# Potentiometer_ADC.net
KiCad netlist of a schematic drawn in EAGLE
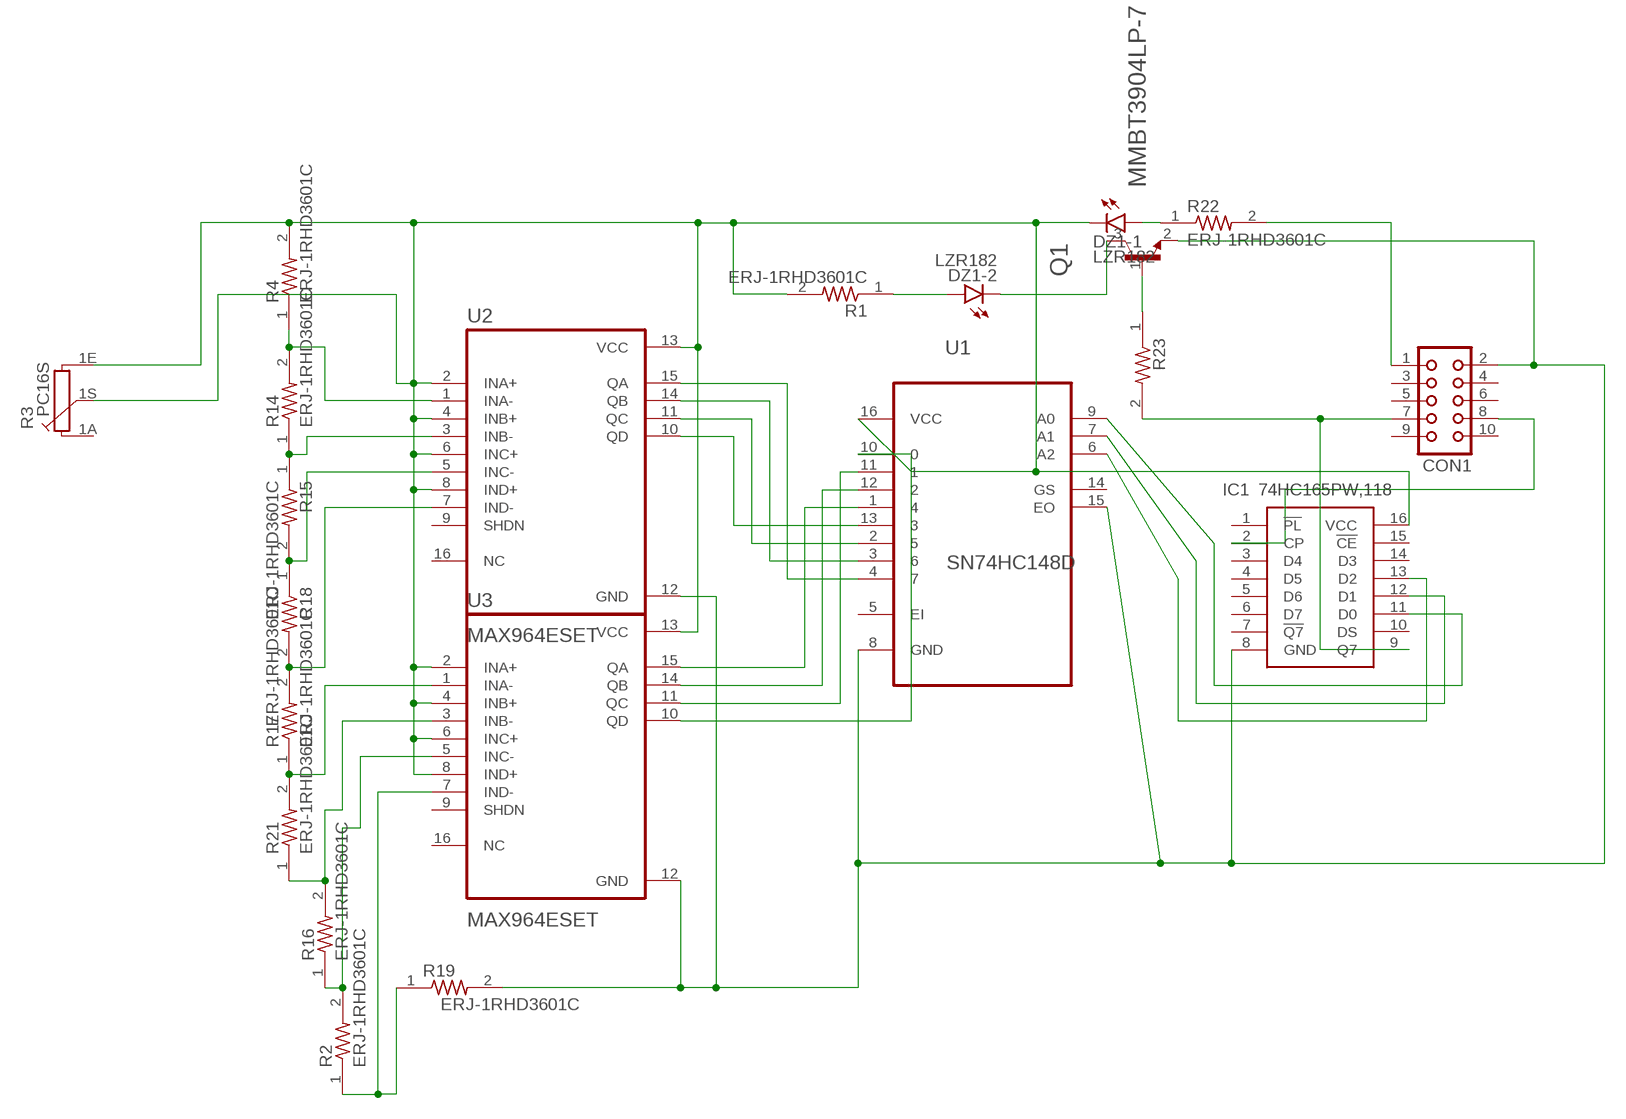
[diagram p0: schematic, sheet 1]

(export (version "E")
  (design (tool "Eeschema 10.0.6"))
  (components
    (comp (ref "CON1")
      (value "CON10L")
      (footprint "eagle-import:CON10L")
      (libsource (lib "eagle-import") (part "CON10L"))
    )
    (comp (ref "DZ1")
      (value "LZR182")
      (footprint "eagle-import:LZR182")
      (libsource (lib "eagle-import") (part "LZR182"))
    )
    (comp (ref "IC1")
      (value "74HC165PW,118")
      (footprint "eagle-import:SOP65P640X110-16N")
      (fields (field (name "MOUSER_PART_NUMBER") "771-74HC165PW-T"))
      (libsource (lib "eagle-import") (part "74HC165PW,118"))
    )
    (comp (ref "Q1")
      (value "MMBT3904LP-7")
      (footprint "eagle-import:DFN101X61X53-3N")
      (fields (field (name "DIGI-KEY_PART_NUMBER") "MMBT3904LP-7DICT-ND") (field (name "MF") "Diodes Inc."))
      (libsource (lib "eagle-import") (part "MMBT3904LP-7"))
    )
    (comp (ref "R1")
      (value "ERJ-1RHD3601C")
      (footprint "eagle-import:RESC0603X26N")
      (fields (field (name "MF") "Panasonic"))
      (libsource (lib "eagle-import") (part "ERJ-1RHD3601C"))
    )
    (comp (ref "R2")
      (value "ERJ-1RHD3601C")
      (footprint "eagle-import:RESC0603X26N")
      (fields (field (name "MF") "Panasonic"))
      (libsource (lib "eagle-import") (part "ERJ-1RHD3601C"))
    )
    (comp (ref "R3")
      (value "PC16S")
      (footprint "eagle-import:PC16S")
      (libsource (lib "eagle-import") (part "PC16S"))
    )
    (comp (ref "R4")
      (value "ERJ-1RHD3601C")
      (footprint "eagle-import:RESC0603X26N")
      (fields (field (name "MF") "Panasonic"))
      (libsource (lib "eagle-import") (part "ERJ-1RHD3601C"))
    )
    (comp (ref "R14")
      (value "ERJ-1RHD3601C")
      (footprint "eagle-import:RESC0603X26N")
      (fields (field (name "MF") "Panasonic"))
      (libsource (lib "eagle-import") (part "ERJ-1RHD3601C"))
    )
    (comp (ref "R15")
      (value "ERJ-1RHD3601C")
      (footprint "eagle-import:RESC0603X26N")
      (fields (field (name "MF") "Panasonic"))
      (libsource (lib "eagle-import") (part "ERJ-1RHD3601C"))
    )
    (comp (ref "R16")
      (value "ERJ-1RHD3601C")
      (footprint "eagle-import:RESC0603X26N")
      (fields (field (name "MF") "Panasonic"))
      (libsource (lib "eagle-import") (part "ERJ-1RHD3601C"))
    )
    (comp (ref "R17")
      (value "ERJ-1RHD3601C")
      (footprint "eagle-import:RESC0603X26N")
      (fields (field (name "MF") "Panasonic"))
      (libsource (lib "eagle-import") (part "ERJ-1RHD3601C"))
    )
    (comp (ref "R18")
      (value "ERJ-1RHD3601C")
      (footprint "eagle-import:RESC0603X26N")
      (fields (field (name "MF") "Panasonic"))
      (libsource (lib "eagle-import") (part "ERJ-1RHD3601C"))
    )
    (comp (ref "R19")
      (value "ERJ-1RHD3601C")
      (footprint "eagle-import:RESC0603X26N")
      (fields (field (name "MF") "Panasonic"))
      (libsource (lib "eagle-import") (part "ERJ-1RHD3601C"))
    )
    (comp (ref "R21")
      (value "ERJ-1RHD3601C")
      (footprint "eagle-import:RESC0603X26N")
      (fields (field (name "MF") "Panasonic"))
      (libsource (lib "eagle-import") (part "ERJ-1RHD3601C"))
    )
    (comp (ref "R22")
      (value "ERJ-1RHD3601C")
      (footprint "eagle-import:RESC0603X26N")
      (fields (field (name "MF") "Panasonic"))
      (libsource (lib "eagle-import") (part "ERJ-1RHD3601C"))
    )
    (comp (ref "R23")
      (value "ERJ-1RHD3601C")
      (footprint "eagle-import:RESC0603X26N")
      (fields (field (name "MF") "Panasonic"))
      (libsource (lib "eagle-import") (part "ERJ-1RHD3601C"))
    )
    (comp (ref "U1")
      (value "SN74HC148D")
      (footprint "eagle-import:SOIC127P600X175-16N")
      (fields (field (name "MF") "Texas Instruments"))
      (libsource (lib "eagle-import") (part "SN74HC148D"))
    )
    (comp (ref "U2")
      (value "MAX964ESET")
      (footprint "eagle-import:SOIC127P600X175-16N")
      (fields (field (name "MF") "Maxim Integrated") (field (name "MP") "MAX964ESE+"))
      (libsource (lib "eagle-import") (part "MAX964ESET"))
    )
    (comp (ref "U3")
      (value "MAX964ESET")
      (footprint "eagle-import:SOIC127P600X175-16N")
      (fields (field (name "MF") "Maxim Integrated") (field (name "MP") "MAX964ESE+"))
      (libsource (lib "eagle-import") (part "MAX964ESET"))
    )
  )
  (nets
    (net (code "1") (name "Net-(CON1-Pad1)") (class "Default")
      (node (ref "CON1") (pin "1") (pinfunction "1_1") (pintype "passive"))
      (node (ref "R22") (pin "2") (pinfunction "2_2") (pintype "passive"))
    )
    (net (code "2") (name "Net-(DZ1A-A)") (class "Default")
      (node (ref "DZ1") (pin "A1") (pinfunction "A_A1") (pintype "passive"))
      (node (ref "R22") (pin "1") (pinfunction "1_1") (pintype "passive"))
    )
    (net (code "3") (name "Net-(DZ1A-C)") (class "Default")
      (node (ref "DZ1") (pin "K1") (pinfunction "C_K1") (pintype "passive"))
      (node (ref "IC1") (pin "16") (pinfunction "VCC_16") (pintype "bidirectional"))
      (node (ref "R1") (pin "2") (pinfunction "2_2") (pintype "passive"))
      (node (ref "R3") (pin "1E") (pinfunction "1E_1E") (pintype "passive"))
      (node (ref "R3") (pin "1S") (pinfunction "1S_1S") (pintype "passive"))
      (node (ref "R4") (pin "2") (pinfunction "2_2") (pintype "passive"))
      (node (ref "U1") (pin "16") (pinfunction "VCC_16") (pintype "power_in"))
      (node (ref "U2") (pin "13") (pinfunction "VCC_13") (pintype "power_in"))
      (node (ref "U2") (pin "2") (pinfunction "INA+_2") (pintype "input"))
      (node (ref "U2") (pin "4") (pinfunction "INB+_4") (pintype "input"))
      (node (ref "U2") (pin "6") (pinfunction "INC+_6") (pintype "input"))
      (node (ref "U2") (pin "8") (pinfunction "IND+_8") (pintype "input"))
      (node (ref "U3") (pin "13") (pinfunction "VCC_13") (pintype "power_in"))
      (node (ref "U3") (pin "2") (pinfunction "INA+_2") (pintype "input"))
      (node (ref "U3") (pin "4") (pinfunction "INB+_4") (pintype "input"))
      (node (ref "U3") (pin "6") (pinfunction "INC+_6") (pintype "input"))
      (node (ref "U3") (pin "8") (pinfunction "IND+_8") (pintype "input"))
    )
    (net (code "4") (name "Net-(DZ1B-A)") (class "Default")
      (node (ref "DZ1") (pin "A2") (pinfunction "A_A2") (pintype "passive"))
      (node (ref "R1") (pin "1") (pinfunction "1_1") (pintype "passive"))
    )
    (net (code "5") (name "Net-(DZ1B-C)") (class "Default")
      (node (ref "DZ1") (pin "K2") (pinfunction "C_K2") (pintype "passive"))
      (node (ref "Q1") (pin "3") (pinfunction "C_3") (pintype "passive"))
    )
    (net (code "6") (name "Net-(IC1-CP)") (class "Default")
      (node (ref "CON1") (pin "8") (pinfunction "8_8") (pintype "passive"))
      (node (ref "IC1") (pin "2") (pinfunction "CP_2") (pintype "bidirectional"))
    )
    (net (code "7") (name "Net-(IC1-D0)") (class "Default")
      (node (ref "IC1") (pin "11") (pinfunction "D0_11") (pintype "bidirectional"))
      (node (ref "U1") (pin "9") (pinfunction "A0_9") (pintype "output"))
    )
    (net (code "8") (name "Net-(IC1-D1)") (class "Default")
      (node (ref "IC1") (pin "12") (pinfunction "D1_12") (pintype "bidirectional"))
      (node (ref "U1") (pin "7") (pinfunction "A1_7") (pintype "output"))
    )
    (net (code "9") (name "Net-(IC1-D2)") (class "Default")
      (node (ref "IC1") (pin "13") (pinfunction "D2_13") (pintype "bidirectional"))
      (node (ref "U1") (pin "6") (pinfunction "A2_6") (pintype "output"))
    )
    (net (code "10") (name "Net-(IC1-GND)") (class "Default")
      (node (ref "CON1") (pin "2") (pinfunction "2_2") (pintype "passive"))
      (node (ref "IC1") (pin "8") (pinfunction "GND_8") (pintype "bidirectional"))
      (node (ref "Q1") (pin "2") (pinfunction "E_2") (pintype "passive"))
      (node (ref "R19") (pin "2") (pinfunction "2_2") (pintype "passive"))
      (node (ref "U1") (pin "15") (pinfunction "EO_15") (pintype "output"))
      (node (ref "U1") (pin "8") (pinfunction "GND_8") (pintype "passive"))
      (node (ref "U2") (pin "12") (pinfunction "GND_12") (pintype "power_in"))
      (node (ref "U3") (pin "12") (pinfunction "GND_12") (pintype "power_in"))
    )
    (net (code "11") (name "Net-(IC1-Q7)") (class "Default")
      (node (ref "CON1") (pin "7") (pinfunction "7_7") (pintype "passive"))
      (node (ref "IC1") (pin "9") (pinfunction "Q7_9") (pintype "bidirectional"))
      (node (ref "R23") (pin "2") (pinfunction "2_2") (pintype "passive"))
    )
    (net (code "12") (name "Net-(Q1-B)") (class "Default")
      (node (ref "Q1") (pin "1") (pinfunction "B_1") (pintype "passive"))
      (node (ref "R23") (pin "1") (pinfunction "1_1") (pintype "passive"))
    )
    (net (code "13") (name "Net-(U1-0)") (class "Default")
      (node (ref "U1") (pin "10") (pinfunction "0_10") (pintype "input"))
      (node (ref "U3") (pin "10") (pinfunction "QD_10") (pintype "output"))
    )
    (net (code "14") (name "Net-(U1-1)") (class "Default")
      (node (ref "U1") (pin "11") (pinfunction "1_11") (pintype "input"))
      (node (ref "U3") (pin "11") (pinfunction "QC_11") (pintype "output"))
    )
    (net (code "15") (name "Net-(U1-2)") (class "Default")
      (node (ref "U1") (pin "12") (pinfunction "2_12") (pintype "input"))
      (node (ref "U3") (pin "14") (pinfunction "QB_14") (pintype "output"))
    )
    (net (code "16") (name "Net-(U1-3)") (class "Default")
      (node (ref "U1") (pin "13") (pinfunction "3_13") (pintype "input"))
      (node (ref "U2") (pin "10") (pinfunction "QD_10") (pintype "output"))
    )
    (net (code "17") (name "Net-(U1-4)") (class "Default")
      (node (ref "U1") (pin "1") (pinfunction "4_1") (pintype "input"))
      (node (ref "U3") (pin "15") (pinfunction "QA_15") (pintype "output"))
    )
    (net (code "18") (name "Net-(U1-5)") (class "Default")
      (node (ref "U1") (pin "2") (pinfunction "5_2") (pintype "input"))
      (node (ref "U2") (pin "11") (pinfunction "QC_11") (pintype "output"))
    )
    (net (code "19") (name "Net-(U1-6)") (class "Default")
      (node (ref "U1") (pin "3") (pinfunction "6_3") (pintype "input"))
      (node (ref "U2") (pin "14") (pinfunction "QB_14") (pintype "output"))
    )
    (net (code "20") (name "Net-(U1-7)") (class "Default")
      (node (ref "U1") (pin "4") (pinfunction "7_4") (pintype "input"))
      (node (ref "U2") (pin "15") (pinfunction "QA_15") (pintype "output"))
    )
    (net (code "21") (name "Net-(U2-INA-)") (class "Default")
      (node (ref "R14") (pin "2") (pinfunction "2_2") (pintype "passive"))
      (node (ref "R4") (pin "1") (pinfunction "1_1") (pintype "passive"))
      (node (ref "U2") (pin "1") (pinfunction "INA-_1") (pintype "input"))
    )
    (net (code "22") (name "Net-(U2-INB-)") (class "Default")
      (node (ref "R14") (pin "1") (pinfunction "1_1") (pintype "passive"))
      (node (ref "R15") (pin "1") (pinfunction "1_1") (pintype "passive"))
      (node (ref "U2") (pin "3") (pinfunction "INB-_3") (pintype "input"))
    )
    (net (code "23") (name "Net-(U2-INC-)") (class "Default")
      (node (ref "R15") (pin "2") (pinfunction "2_2") (pintype "passive"))
      (node (ref "R18") (pin "1") (pinfunction "1_1") (pintype "passive"))
      (node (ref "U2") (pin "5") (pinfunction "INC-_5") (pintype "input"))
    )
    (net (code "24") (name "Net-(U2-IND-)") (class "Default")
      (node (ref "R17") (pin "2") (pinfunction "2_2") (pintype "passive"))
      (node (ref "R18") (pin "2") (pinfunction "2_2") (pintype "passive"))
      (node (ref "U2") (pin "7") (pinfunction "IND-_7") (pintype "input"))
    )
    (net (code "25") (name "Net-(U3-INA-)") (class "Default")
      (node (ref "R17") (pin "1") (pinfunction "1_1") (pintype "passive"))
      (node (ref "R21") (pin "2") (pinfunction "2_2") (pintype "passive"))
      (node (ref "U3") (pin "1") (pinfunction "INA-_1") (pintype "input"))
    )
    (net (code "26") (name "Net-(U3-INB-)") (class "Default")
      (node (ref "R16") (pin "2") (pinfunction "2_2") (pintype "passive"))
      (node (ref "R21") (pin "1") (pinfunction "1_1") (pintype "passive"))
      (node (ref "U3") (pin "3") (pinfunction "INB-_3") (pintype "input"))
    )
    (net (code "27") (name "Net-(U3-INC-)") (class "Default")
      (node (ref "R16") (pin "1") (pinfunction "1_1") (pintype "passive"))
      (node (ref "R2") (pin "2") (pinfunction "2_2") (pintype "passive"))
      (node (ref "U3") (pin "5") (pinfunction "INC-_5") (pintype "input"))
    )
    (net (code "28") (name "Net-(U3-IND-)") (class "Default")
      (node (ref "R19") (pin "1") (pinfunction "1_1") (pintype "passive"))
      (node (ref "R2") (pin "1") (pinfunction "1_1") (pintype "passive"))
      (node (ref "U3") (pin "7") (pinfunction "IND-_7") (pintype "input"))
    )
    (net (code "29") (name "unconnected-(CON1-Pad3)") (class "Default")
      (node (ref "CON1") (pin "3") (pinfunction "3_3") (pintype "passive"))
    )
    (net (code "30") (name "unconnected-(CON1-Pad4)") (class "Default")
      (node (ref "CON1") (pin "4") (pinfunction "4_4") (pintype "passive"))
    )
    (net (code "31") (name "unconnected-(CON1-Pad5)") (class "Default")
      (node (ref "CON1") (pin "5") (pinfunction "5_5") (pintype "passive"))
    )
    (net (code "32") (name "unconnected-(CON1-Pad6)") (class "Default")
      (node (ref "CON1") (pin "6") (pinfunction "6_6") (pintype "passive"))
    )
    (net (code "33") (name "unconnected-(CON1-Pad9)") (class "Default")
      (node (ref "CON1") (pin "9") (pinfunction "9_9") (pintype "passive"))
    )
    (net (code "34") (name "unconnected-(CON1-Pad10)") (class "Default")
      (node (ref "CON1") (pin "10") (pinfunction "10_10") (pintype "passive"))
    )
    (net (code "35") (name "unconnected-(IC1-D3-Pad14)") (class "Default")
      (node (ref "IC1") (pin "14") (pinfunction "D3_14") (pintype "bidirectional"))
    )
    (net (code "36") (name "unconnected-(IC1-D4-Pad3)") (class "Default")
      (node (ref "IC1") (pin "3") (pinfunction "D4_3") (pintype "bidirectional"))
    )
    (net (code "37") (name "unconnected-(IC1-D5-Pad4)") (class "Default")
      (node (ref "IC1") (pin "4") (pinfunction "D5_4") (pintype "bidirectional"))
    )
    (net (code "38") (name "unconnected-(IC1-D6-Pad5)") (class "Default")
      (node (ref "IC1") (pin "5") (pinfunction "D6_5") (pintype "bidirectional"))
    )
    (net (code "39") (name "unconnected-(IC1-D7-Pad6)") (class "Default")
      (node (ref "IC1") (pin "6") (pinfunction "D7_6") (pintype "bidirectional"))
    )
    (net (code "40") (name "unconnected-(IC1-DS-Pad10)") (class "Default")
      (node (ref "IC1") (pin "10") (pinfunction "DS_10") (pintype "bidirectional"))
    )
    (net (code "41") (name "unconnected-(IC1-~{CE}-Pad15)") (class "Default")
      (node (ref "IC1") (pin "15") (pinfunction "~{CE}_15") (pintype "bidirectional"))
    )
    (net (code "42") (name "unconnected-(IC1-~{PL}-Pad1)") (class "Default")
      (node (ref "IC1") (pin "1") (pinfunction "~{PL}_1") (pintype "bidirectional"))
    )
    (net (code "43") (name "unconnected-(IC1-~{Q7}-Pad7)") (class "Default")
      (node (ref "IC1") (pin "7") (pinfunction "~{Q7}_7") (pintype "bidirectional"))
    )
    (net (code "44") (name "unconnected-(R3-Pad1A)") (class "Default")
      (node (ref "R3") (pin "1A") (pinfunction "1A_1A") (pintype "passive"))
    )
    (net (code "45") (name "unconnected-(U1-EI-Pad5)") (class "Default")
      (node (ref "U1") (pin "5") (pinfunction "EI_5") (pintype "input"))
    )
    (net (code "46") (name "unconnected-(U1-GS-Pad14)") (class "Default")
      (node (ref "U1") (pin "14") (pinfunction "GS_14") (pintype "output"))
    )
    (net (code "47") (name "unconnected-(U2-NC-Pad16)") (class "Default")
      (node (ref "U2") (pin "16") (pinfunction "NC_16") (pintype "bidirectional"))
    )
    (net (code "48") (name "unconnected-(U2-SHDN-Pad9)") (class "Default")
      (node (ref "U2") (pin "9") (pinfunction "SHDN_9") (pintype "input"))
    )
    (net (code "49") (name "unconnected-(U3-NC-Pad16)") (class "Default")
      (node (ref "U3") (pin "16") (pinfunction "NC_16") (pintype "bidirectional"))
    )
    (net (code "50") (name "unconnected-(U3-SHDN-Pad9)") (class "Default")
      (node (ref "U3") (pin "9") (pinfunction "SHDN_9") (pintype "input"))
    )
  )
)
